# boxer_analog.net
KiCad netlist of a schematic drawn in Altium Designer
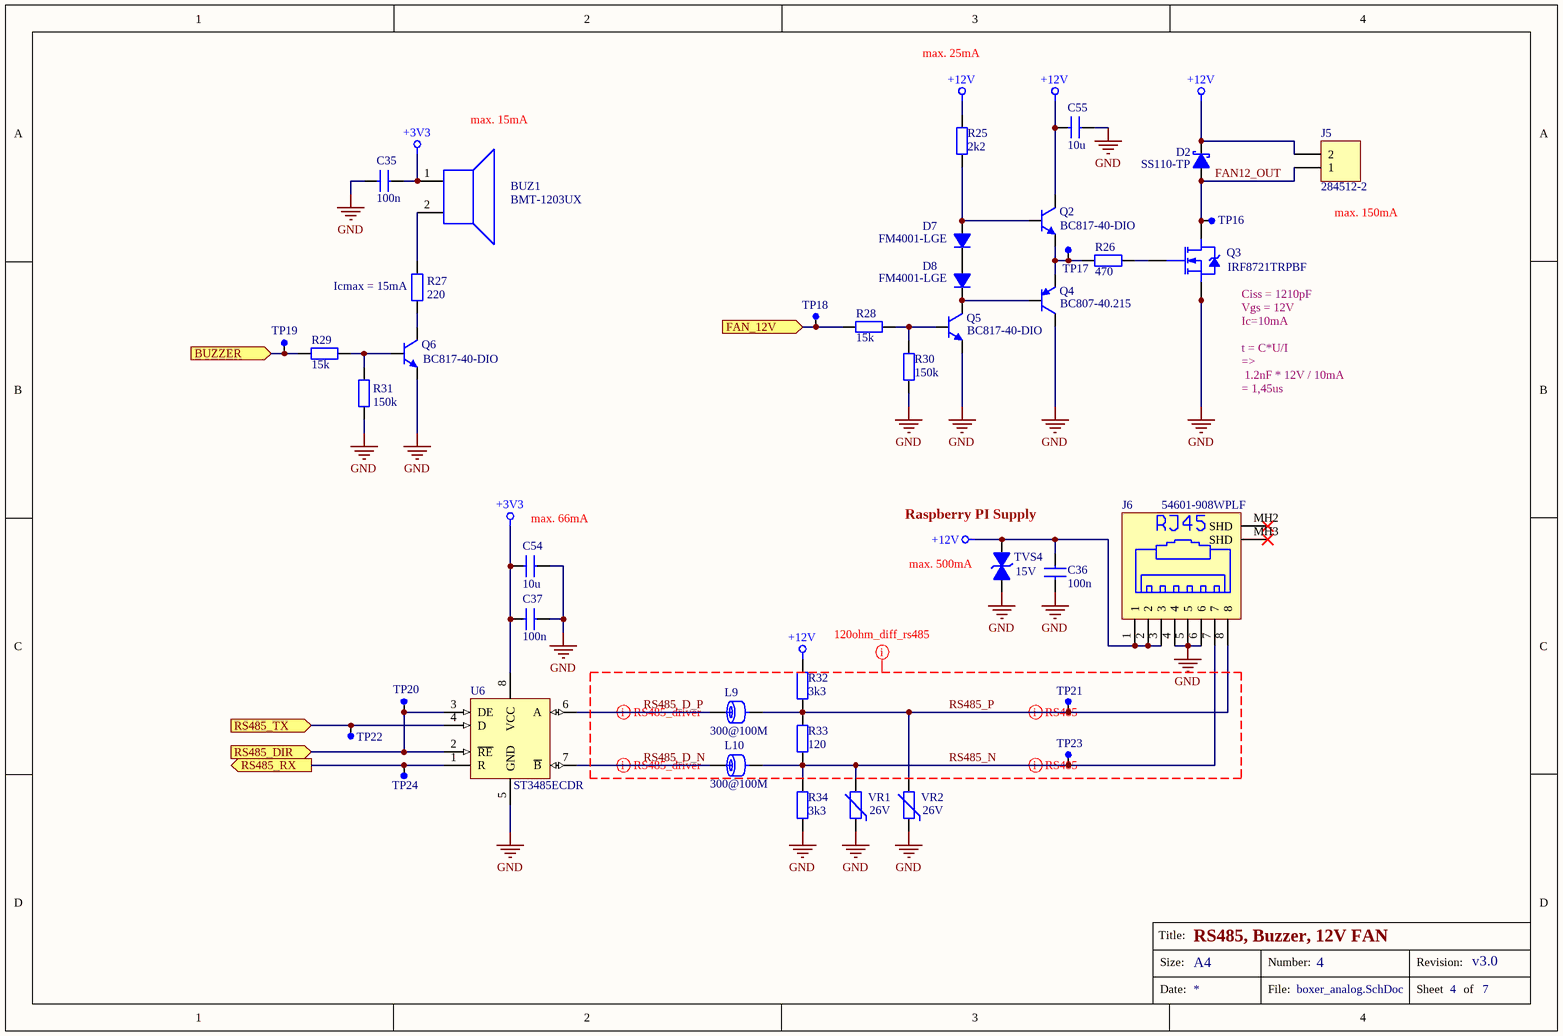
[diagram p0: boxer_analog.SchDoc]

(export (version "E")
  (design (tool "Eeschema 10.0.6"))
  (components
    (comp (ref "BUZ1")
      (value "BMT-1203UX")
      (footprint "buzzer 7.6mm")
      (libsource (lib "boxer_pas") (part "Buzzer"))
    )
    (comp (ref "C35")
      (value "100n")
      (footprint "C_0805")
      (description "Capacitor")
      (libsource (lib "boxer_pas") (part "Capacitor"))
    )
    (comp (ref "C36")
      (value "100n")
      (footprint "C_0805")
      (description "Capacitor")
      (libsource (lib "boxer_pas") (part "Capacitor"))
    )
    (comp (ref "C37")
      (value "100n")
      (footprint "C_0805")
      (description "Capacitor")
      (libsource (lib "boxer_pas") (part "Capacitor"))
    )
    (comp (ref "C54")
      (value "10u")
      (footprint "C_1206")
      (description "Capacitor")
      (fields (field (name "Comment") "TME: CL31A226MOCLNNC"))
      (libsource (lib "boxer_pas") (part "Capacitor"))
    )
    (comp (ref "C55")
      (value "10u")
      (footprint "C_1206")
      (description "Capacitor")
      (fields (field (name "Comment") "TME: CL31A226MOCLNNC"))
      (libsource (lib "boxer_pas") (part "Capacitor"))
    )
    (comp (ref "D2")
      (value "SS110-TP")
      (footprint "D_SMA")
      (description "Schottky Diode")
      (libsource (lib "boxer_pas") (part "Diode Schottky"))
    )
    (comp (ref "D7")
      (value "FM4001-LGE")
      (footprint "SOD123F")
      (description "Diode")
      (libsource (lib "boxer_pas") (part "Diode"))
    )
    (comp (ref "D8")
      (value "FM4001-LGE")
      (footprint "SOD123F")
      (description "Diode")
      (libsource (lib "boxer_pas") (part "Diode"))
    )
    (comp (ref "J5")
      (value "284512-2")
      (footprint "284512-2")
      (description "Header, 2-Pin")
      (libsource (lib "boxer_mechanical") (part "Header 2"))
    )
    (comp (ref "J6")
      (value "54601-908WPLF")
      (footprint "RJ45_54601-908WPLF")
      (description "RJ45 Socket, 8pin, No Key, Molex MX-95001-2881")
      (libsource (lib "boxer_mechanical") (part "RJ45-8"))
    )
    (comp (ref "L9")
      (value "300@100M")
      (footprint "L_0805")
      (description "Ferrite Bead")
      (fields (field (name "Comment") "742792031"))
      (libsource (lib "boxer_pas") (part "FB"))
    )
    (comp (ref "L10")
      (value "300@100M")
      (footprint "L_0805")
      (description "Ferrite Bead")
      (fields (field (name "Comment") "742792031"))
      (libsource (lib "boxer_pas") (part "FB"))
    )
    (comp (ref "Q2")
      (value "BC817-40-DIO")
      (footprint "SOT-23")
      (description "NPN Bipolar Transistor")
      (libsource (lib "boxer_pas") (part "NPN"))
    )
    (comp (ref "Q3")
      (value "IRF8721TRPBF")
      (footprint "boxer_ic:SO8")
      (description "N-Channel MOSFET")
      (libsource (lib "boxer_pas") (part "MOSFET-N_SO8"))
    )
    (comp (ref "Q4")
      (value "BC807-40.215")
      (footprint "SOT-23")
      (description "PNP")
      (libsource (lib "boxer_pas") (part "PNP"))
    )
    (comp (ref "Q5")
      (value "BC817-40-DIO")
      (footprint "SOT-23")
      (description "NPN Bipolar Transistor")
      (libsource (lib "boxer_pas") (part "NPN"))
    )
    (comp (ref "Q6")
      (value "BC817-40-DIO")
      (footprint "SOT-23")
      (description "NPN Bipolar Transistor")
      (libsource (lib "boxer_pas") (part "NPN"))
    )
    (comp (ref "R25")
      (value "2k2")
      (footprint "R_0805")
      (description "Resistor")
      (libsource (lib "") (part "Resistor_1"))
    )
    (comp (ref "R26")
      (value "470")
      (footprint "R_1206")
      (description "Resistor")
      (libsource (lib "") (part "Resistor_2"))
    )
    (comp (ref "R27")
      (value "220")
      (footprint "R_0805")
      (description "Resistor")
      (libsource (lib "") (part "Resistor_1"))
    )
    (comp (ref "R28")
      (value "15k")
      (footprint "R_0805")
      (description "Resistor")
      (libsource (lib "boxer_pas") (part "Resistor"))
    )
    (comp (ref "R29")
      (value "15k")
      (footprint "R_0805")
      (description "Resistor")
      (libsource (lib "boxer_pas") (part "Resistor"))
    )
    (comp (ref "R30")
      (value "150k")
      (footprint "R_0805")
      (description "Resistor")
      (libsource (lib "") (part "Resistor_1"))
    )
    (comp (ref "R31")
      (value "150k")
      (footprint "R_0805")
      (description "Resistor")
      (libsource (lib "") (part "Resistor_1"))
    )
    (comp (ref "R32")
      (value "3k3")
      (footprint "R_0805")
      (description "Resistor")
      (libsource (lib "") (part "Resistor_1"))
    )
    (comp (ref "R33")
      (value "120")
      (footprint "R_0805")
      (description "Resistor")
      (libsource (lib "") (part "Resistor_1"))
    )
    (comp (ref "R34")
      (value "3k3")
      (footprint "R_0805")
      (description "Resistor")
      (libsource (lib "") (part "Resistor_1"))
    )
    (comp (ref "TP16")
      (value "TEST PAD")
      (footprint "PIN")
      (description "PAD 1.5mm")
      (libsource (lib "boxer_mechanical") (part "TEST_PAD"))
    )
    (comp (ref "TP17")
      (value "TEST PAD")
      (footprint "PIN")
      (description "PAD 1.5mm")
      (libsource (lib "boxer_mechanical") (part "TEST_PAD"))
    )
    (comp (ref "TP18")
      (value "TEST PAD")
      (footprint "PIN")
      (description "PAD 1.5mm")
      (libsource (lib "boxer_mechanical") (part "TEST_PAD"))
    )
    (comp (ref "TP19")
      (value "TEST PAD")
      (footprint "PIN")
      (description "PAD 1.5mm")
      (libsource (lib "boxer_mechanical") (part "TEST_PAD"))
    )
    (comp (ref "TP20")
      (value "TEST PAD")
      (footprint "PIN")
      (description "PAD 1.5mm")
      (libsource (lib "boxer_mechanical") (part "TEST_PAD"))
    )
    (comp (ref "TP21")
      (value "TEST PAD")
      (footprint "PIN")
      (description "PAD 1.5mm")
      (libsource (lib "boxer_mechanical") (part "TEST_PAD"))
    )
    (comp (ref "TP22")
      (value "TEST PAD")
      (footprint "PIN")
      (description "PAD 1.5mm")
      (libsource (lib "boxer_mechanical") (part "TEST_PAD"))
    )
    (comp (ref "TP23")
      (value "TEST PAD")
      (footprint "PIN")
      (description "PAD 1.5mm")
      (libsource (lib "boxer_mechanical") (part "TEST_PAD"))
    )
    (comp (ref "TP24")
      (value "TEST PAD")
      (footprint "PIN")
      (description "PAD 1.5mm")
      (libsource (lib "boxer_mechanical") (part "TEST_PAD"))
    )
    (comp (ref "TVS4")
      (value "15V")
      (footprint "D_SMB")
      (description "Transil")
      (fields (field (name "Comment") "SM6T15CA"))
      (libsource (lib "boxer_pas") (part "Transil"))
    )
    (comp (ref "U6")
      (value "ST3485ECDR")
      (footprint "SO8")
      (description "RS-422/RS-485 Interface IC Hi-Spd Lo Pwr Trans")
      (libsource (lib "boxer_ic") (part "ST485BDR"))
    )
    (comp (ref "VR1")
      (value "26V")
      (footprint "VR_0805")
      (description "34.5V 20A Varistor 1 Circuit Surface Mount, MLCV 0805 (2012 Metric)")
      (fields (field (name "Comment") "AMCV-0805-260-C800N-T"))
      (libsource (lib "boxer_pas") (part "Varistor"))
    )
    (comp (ref "VR2")
      (value "26V")
      (footprint "VR_0805")
      (description "34.5V 20A Varistor 1 Circuit Surface Mount, MLCV 0805 (2012 Metric)")
      (fields (field (name "Comment") "AMCV-0805-260-C800N-T"))
      (libsource (lib "boxer_pas") (part "Varistor"))
    )
  )
  (nets
    (net (code "1") (name "+3V3") (class "Default")
      (node (ref "BUZ1") (pin "1") (pinfunction "1_1") (pintype "passive"))
      (node (ref "C35") (pin "2") (pinfunction "2_2") (pintype "passive"))
      (node (ref "C37") (pin "1") (pinfunction "1_1") (pintype "passive"))
      (node (ref "C54") (pin "2") (pinfunction "2_2") (pintype "passive"))
      (node (ref "U6") (pin "8") (pinfunction "VCC_8") (pintype "power_in"))
    )
    (net (code "2") (name "+12V") (class "Default")
      (node (ref "C36") (pin "1") (pinfunction "1_1") (pintype "passive"))
      (node (ref "C55") (pin "1") (pinfunction "1_1") (pintype "passive"))
      (node (ref "D2") (pin "2") (pinfunction "K_2") (pintype "passive"))
      (node (ref "J5") (pin "2") (pinfunction "2_2") (pintype "passive"))
      (node (ref "J6") (pin "1") (pinfunction "1_1") (pintype "passive"))
      (node (ref "J6") (pin "2") (pinfunction "2_2") (pintype "passive"))
      (node (ref "J6") (pin "3") (pinfunction "3_3") (pintype "passive"))
      (node (ref "Q2") (pin "3") (pinfunction "C_3") (pintype "passive"))
      (node (ref "R25") (pin "2") (pinfunction "2_2") (pintype "passive"))
      (node (ref "R32") (pin "2") (pinfunction "2_2") (pintype "passive"))
      (node (ref "TVS4") (pin "1") (pinfunction "A_1") (pintype "passive"))
    )
    (net (code "3") (name "/BUZZER") (class "Default")
      (node (ref "R29") (pin "1") (pinfunction "1_1") (pintype "passive"))
      (node (ref "TP19") (pin "1") (pinfunction "1_1") (pintype "passive"))
    )
    (net (code "4") (name "/FAN12_OUT") (class "Default")
      (node (ref "D2") (pin "1") (pinfunction "A_1") (pintype "passive"))
      (node (ref "J5") (pin "1") (pinfunction "1_1") (pintype "passive"))
      (node (ref "Q3") (pin "5") (pinfunction "D_5") (pintype "passive"))
      (node (ref "Q3") (pin "6") (pinfunction "D_6") (pintype "passive"))
      (node (ref "Q3") (pin "7") (pinfunction "D_7") (pintype "passive"))
      (node (ref "Q3") (pin "8") (pinfunction "D_8") (pintype "passive"))
      (node (ref "TP16") (pin "1") (pinfunction "1_1") (pintype "passive"))
    )
    (net (code "5") (name "/FAN_12V") (class "Default")
      (node (ref "R28") (pin "1") (pinfunction "1_1") (pintype "passive"))
      (node (ref "TP18") (pin "1") (pinfunction "1_1") (pintype "passive"))
    )
    (net (code "6") (name "/RS485_DIR") (class "Default")
      (node (ref "TP20") (pin "1") (pinfunction "1_1") (pintype "passive"))
      (node (ref "U6") (pin "2") (pinfunction "~{RE}_2") (pintype "input"))
      (node (ref "U6") (pin "3") (pinfunction "DE_3") (pintype "input"))
    )
    (net (code "7") (name "/RS485_D_N") (class "Default")
      (node (ref "L10") (pin "1") (pinfunction "1_1") (pintype "passive"))
      (node (ref "U6") (pin "7") (pinfunction "~{B}_7") (pintype "bidirectional"))
    )
    (net (code "8") (name "/RS485_D_P") (class "Default")
      (node (ref "L9") (pin "1") (pinfunction "1_1") (pintype "passive"))
      (node (ref "U6") (pin "6") (pinfunction "A_6") (pintype "bidirectional"))
    )
    (net (code "9") (name "/RS485_N") (class "Default")
      (node (ref "J6") (pin "7") (pinfunction "7_7") (pintype "passive"))
      (node (ref "L10") (pin "2") (pinfunction "2_2") (pintype "passive"))
      (node (ref "R33") (pin "1") (pinfunction "1_1") (pintype "passive"))
      (node (ref "R34") (pin "2") (pinfunction "2_2") (pintype "passive"))
      (node (ref "TP23") (pin "1") (pinfunction "1_1") (pintype "passive"))
      (node (ref "VR1") (pin "1") (pinfunction "1_1") (pintype "passive"))
    )
    (net (code "10") (name "/RS485_P") (class "Default")
      (node (ref "J6") (pin "8") (pinfunction "8_8") (pintype "passive"))
      (node (ref "L9") (pin "2") (pinfunction "2_2") (pintype "passive"))
      (node (ref "R32") (pin "1") (pinfunction "1_1") (pintype "passive"))
      (node (ref "R33") (pin "2") (pinfunction "2_2") (pintype "passive"))
      (node (ref "TP21") (pin "1") (pinfunction "1_1") (pintype "passive"))
      (node (ref "VR2") (pin "1") (pinfunction "1_1") (pintype "passive"))
    )
    (net (code "11") (name "/RS485_RX") (class "Default")
      (node (ref "TP24") (pin "1") (pinfunction "1_1") (pintype "passive"))
      (node (ref "U6") (pin "1") (pinfunction "R_1") (pintype "tri_state"))
    )
    (net (code "12") (name "/RS485_TX") (class "Default")
      (node (ref "TP22") (pin "1") (pinfunction "1_1") (pintype "passive"))
      (node (ref "U6") (pin "4") (pinfunction "D_4") (pintype "input"))
    )
    (net (code "13") (name "GND") (class "Default")
      (node (ref "C35") (pin "1") (pinfunction "1_1") (pintype "passive"))
      (node (ref "C36") (pin "2") (pinfunction "2_2") (pintype "passive"))
      (node (ref "C37") (pin "2") (pinfunction "2_2") (pintype "passive"))
      (node (ref "C54") (pin "1") (pinfunction "1_1") (pintype "passive"))
      (node (ref "C55") (pin "2") (pinfunction "2_2") (pintype "passive"))
      (node (ref "J6") (pin "4") (pinfunction "4_4") (pintype "passive"))
      (node (ref "J6") (pin "5") (pinfunction "5_5") (pintype "passive"))
      (node (ref "J6") (pin "6") (pinfunction "6_6") (pintype "passive"))
      (node (ref "Q3") (pin "1") (pinfunction "S_1") (pintype "passive"))
      (node (ref "Q3") (pin "2") (pinfunction "S_2") (pintype "passive"))
      (node (ref "Q3") (pin "3") (pinfunction "S_3") (pintype "passive"))
      (node (ref "Q4") (pin "3") (pinfunction "C_3") (pintype "passive"))
      (node (ref "Q5") (pin "2") (pinfunction "E_2") (pintype "passive"))
      (node (ref "Q6") (pin "2") (pinfunction "E_2") (pintype "passive"))
      (node (ref "R30") (pin "1") (pinfunction "1_1") (pintype "passive"))
      (node (ref "R31") (pin "1") (pinfunction "1_1") (pintype "passive"))
      (node (ref "R34") (pin "1") (pinfunction "1_1") (pintype "passive"))
      (node (ref "TVS4") (pin "2") (pinfunction "K_2") (pintype "passive"))
      (node (ref "U6") (pin "5") (pinfunction "GND_5") (pintype "power_in"))
      (node (ref "VR1") (pin "2") (pinfunction "2_2") (pintype "passive"))
      (node (ref "VR2") (pin "2") (pinfunction "2_2") (pintype "passive"))
    )
    (net (code "14") (name "Net-(BUZ1-Pad2)") (class "Default")
      (node (ref "BUZ1") (pin "2") (pinfunction "2_2") (pintype "passive"))
      (node (ref "R27") (pin "2") (pinfunction "2_2") (pintype "passive"))
    )
    (net (code "15") (name "Net-(D7-A)") (class "Default")
      (node (ref "D7") (pin "1") (pinfunction "A_1") (pintype "passive"))
      (node (ref "Q2") (pin "1") (pinfunction "B_1") (pintype "passive"))
      (node (ref "R25") (pin "1") (pinfunction "1_1") (pintype "passive"))
    )
    (net (code "16") (name "Net-(D7-K)") (class "Default")
      (node (ref "D7") (pin "2") (pinfunction "K_2") (pintype "passive"))
      (node (ref "D8") (pin "1") (pinfunction "A_1") (pintype "passive"))
    )
    (net (code "17") (name "Net-(D8-K)") (class "Default")
      (node (ref "D8") (pin "2") (pinfunction "K_2") (pintype "passive"))
      (node (ref "Q4") (pin "1") (pinfunction "B_1") (pintype "passive"))
      (node (ref "Q5") (pin "3") (pinfunction "C_3") (pintype "passive"))
    )
    (net (code "18") (name "Net-(Q2-E)") (class "Default")
      (node (ref "Q2") (pin "2") (pinfunction "E_2") (pintype "passive"))
      (node (ref "Q4") (pin "2") (pinfunction "E_2") (pintype "passive"))
      (node (ref "R26") (pin "2") (pinfunction "2_2") (pintype "passive"))
      (node (ref "TP17") (pin "1") (pinfunction "1_1") (pintype "passive"))
    )
    (net (code "19") (name "Net-(Q3-G)") (class "Default")
      (node (ref "Q3") (pin "4") (pinfunction "G_4") (pintype "passive"))
      (node (ref "R26") (pin "1") (pinfunction "1_1") (pintype "passive"))
    )
    (net (code "20") (name "Net-(Q5-B)") (class "Default")
      (node (ref "Q5") (pin "1") (pinfunction "B_1") (pintype "passive"))
      (node (ref "R28") (pin "2") (pinfunction "2_2") (pintype "passive"))
      (node (ref "R30") (pin "2") (pinfunction "2_2") (pintype "passive"))
    )
    (net (code "21") (name "Net-(Q6-B)") (class "Default")
      (node (ref "Q6") (pin "1") (pinfunction "B_1") (pintype "passive"))
      (node (ref "R29") (pin "2") (pinfunction "2_2") (pintype "passive"))
      (node (ref "R31") (pin "2") (pinfunction "2_2") (pintype "passive"))
    )
    (net (code "22") (name "Net-(Q6-C)") (class "Default")
      (node (ref "Q6") (pin "3") (pinfunction "C_3") (pintype "passive"))
      (node (ref "R27") (pin "1") (pinfunction "1_1") (pintype "passive"))
    )
    (net (code "23") (name "unconnected-(J6-SHD-PadMH2)") (class "Default")
      (node (ref "J6") (pin "MH2") (pinfunction "SHD_MH2") (pintype "passive+no_connect"))
    )
    (net (code "24") (name "unconnected-(J6-SHD-PadMH3)") (class "Default")
      (node (ref "J6") (pin "MH3") (pinfunction "SHD_MH3") (pintype "passive+no_connect"))
    )
  )
)
